# IRSensorModule.net
KiCad netlist of a schematic drawn in EAGLE
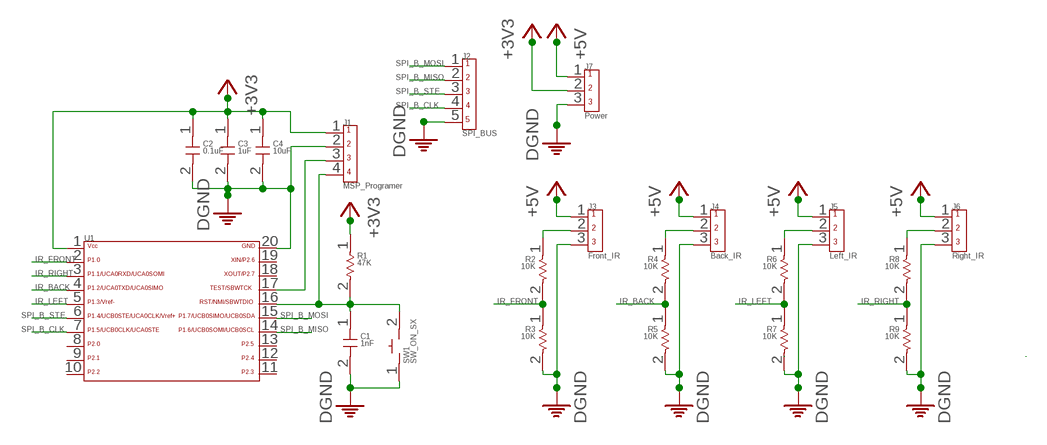
[diagram p0: schematic, sheet 1]

(export (version "E")
  (design (tool "Eeschema 10.0.6"))
  (components
    (comp (ref "C1")
      (value "1nF")
      (footprint "eagle-import:0805")
      (libsource (lib "eagle-import") (part "CAPACITOR_FIXED_0805"))
    )
    (comp (ref "C2")
      (value "0.1uF")
      (footprint "eagle-import:0805")
      (libsource (lib "eagle-import") (part "CAPACITOR_FIXED_0805"))
    )
    (comp (ref "C3")
      (value "1uF")
      (footprint "eagle-import:0805")
      (libsource (lib "eagle-import") (part "CAPACITOR_FIXED_0805"))
    )
    (comp (ref "C4")
      (value "10uF")
      (footprint "eagle-import:0805")
      (libsource (lib "eagle-import") (part "CAPACITOR_FIXED_0805"))
    )
    (comp (ref "J1")
      (value "MSP_Programer")
      (footprint "eagle-import:CON_HEADER_4_100")
      (libsource (lib "eagle-import") (part "CON_HEADER_4PIN_100"))
    )
    (comp (ref "J2")
      (value "SPI_BUS")
      (footprint "eagle-import:CON_HEADER_5_100")
      (libsource (lib "eagle-import") (part "CON_HEADER_5PIN_100"))
    )
    (comp (ref "J3")
      (value "Front_IR")
      (footprint "eagle-import:CON_HEADER_3_100")
      (libsource (lib "eagle-import") (part "CON_HEADER_3PIN_100"))
    )
    (comp (ref "J4")
      (value "Back_IR")
      (footprint "eagle-import:CON_HEADER_3_100")
      (libsource (lib "eagle-import") (part "CON_HEADER_3PIN_100"))
    )
    (comp (ref "J5")
      (value "Left_IR")
      (footprint "eagle-import:CON_HEADER_3_100")
      (libsource (lib "eagle-import") (part "CON_HEADER_3PIN_100"))
    )
    (comp (ref "J6")
      (value "Right_IR")
      (footprint "eagle-import:CON_HEADER_3_100")
      (libsource (lib "eagle-import") (part "CON_HEADER_3PIN_100"))
    )
    (comp (ref "J7")
      (value "Power")
      (footprint "eagle-import:CON_HEADER_3_100")
      (libsource (lib "eagle-import") (part "CON_HEADER_3PIN_100"))
    )
    (comp (ref "R1")
      (value "47K")
      (footprint "eagle-import:0805")
      (libsource (lib "eagle-import") (part "RESISTOR_0805"))
    )
    (comp (ref "R2")
      (value "10K")
      (footprint "eagle-import:0805")
      (libsource (lib "eagle-import") (part "RESISTOR_0805"))
    )
    (comp (ref "R3")
      (value "10K")
      (footprint "eagle-import:0805")
      (libsource (lib "eagle-import") (part "RESISTOR_0805"))
    )
    (comp (ref "R4")
      (value "10K")
      (footprint "eagle-import:0805")
      (libsource (lib "eagle-import") (part "RESISTOR_0805"))
    )
    (comp (ref "R5")
      (value "10K")
      (footprint "eagle-import:0805")
      (libsource (lib "eagle-import") (part "RESISTOR_0805"))
    )
    (comp (ref "R6")
      (value "10K")
      (footprint "eagle-import:0805")
      (libsource (lib "eagle-import") (part "RESISTOR_0805"))
    )
    (comp (ref "R7")
      (value "10K")
      (footprint "eagle-import:0805")
      (libsource (lib "eagle-import") (part "RESISTOR_0805"))
    )
    (comp (ref "R8")
      (value "10K")
      (footprint "eagle-import:0805")
      (libsource (lib "eagle-import") (part "RESISTOR_0805"))
    )
    (comp (ref "R9")
      (value "10K")
      (footprint "eagle-import:0805")
      (libsource (lib "eagle-import") (part "RESISTOR_0805"))
    )
    (comp (ref "SW1")
      (value "SW_ON_SX")
      (footprint "eagle-import:SW_S")
      (libsource (lib "eagle-import") (part "SW_ON_SX"))
    )
    (comp (ref "U1")
      (value "MSP430G2X53/G2X13_20PIN")
      (footprint "eagle-import:SSOP-20")
      (libsource (lib "eagle-import") (part "MSP430G2X53/G2X13_20PIN"))
    )
  )
  (nets
    (net (code "1") (name "+3V3") (class "Default")
      (node (ref "C2") (pin "1") (pinfunction "1_1") (pintype "passive"))
      (node (ref "C3") (pin "1") (pinfunction "1_1") (pintype "passive"))
      (node (ref "C4") (pin "1") (pinfunction "1_1") (pintype "passive"))
      (node (ref "J1") (pin "1") (pinfunction "1_1") (pintype "passive"))
      (node (ref "J7") (pin "2") (pinfunction "2_2") (pintype "passive"))
      (node (ref "R1") (pin "1") (pinfunction "1_1") (pintype "passive"))
      (node (ref "U1") (pin "1") (pinfunction "1_1") (pintype "passive"))
    )
    (net (code "2") (name "+5V") (class "Default")
      (node (ref "J3") (pin "1") (pinfunction "1_1") (pintype "passive"))
      (node (ref "J4") (pin "1") (pinfunction "1_1") (pintype "passive"))
      (node (ref "J5") (pin "1") (pinfunction "1_1") (pintype "passive"))
      (node (ref "J6") (pin "1") (pinfunction "1_1") (pintype "passive"))
      (node (ref "J7") (pin "1") (pinfunction "1_1") (pintype "passive"))
    )
    (net (code "3") (name "/IR_BACK") (class "Default")
      (node (ref "R4") (pin "2") (pinfunction "2_2") (pintype "passive"))
      (node (ref "R5") (pin "1") (pinfunction "1_1") (pintype "passive"))
      (node (ref "U1") (pin "4") (pinfunction "4_4") (pintype "passive"))
    )
    (net (code "4") (name "/IR_FRONT") (class "Default")
      (node (ref "R2") (pin "2") (pinfunction "2_2") (pintype "passive"))
      (node (ref "R3") (pin "1") (pinfunction "1_1") (pintype "passive"))
      (node (ref "U1") (pin "2") (pinfunction "2_2") (pintype "passive"))
    )
    (net (code "5") (name "/IR_LEFT") (class "Default")
      (node (ref "R6") (pin "2") (pinfunction "2_2") (pintype "passive"))
      (node (ref "R7") (pin "1") (pinfunction "1_1") (pintype "passive"))
      (node (ref "U1") (pin "5") (pinfunction "5_5") (pintype "passive"))
    )
    (net (code "6") (name "/IR_RIGHT") (class "Default")
      (node (ref "R8") (pin "2") (pinfunction "2_2") (pintype "passive"))
      (node (ref "R9") (pin "1") (pinfunction "1_1") (pintype "passive"))
      (node (ref "U1") (pin "3") (pinfunction "3_3") (pintype "passive"))
    )
    (net (code "7") (name "/SPI_B_CLK") (class "Default")
      (node (ref "J2") (pin "4") (pinfunction "4_4") (pintype "passive"))
      (node (ref "U1") (pin "7") (pinfunction "7_7") (pintype "passive"))
    )
    (net (code "8") (name "/SPI_B_MISO") (class "Default")
      (node (ref "J2") (pin "2") (pinfunction "2_2") (pintype "passive"))
      (node (ref "U1") (pin "14") (pinfunction "14_14") (pintype "passive"))
    )
    (net (code "9") (name "/SPI_B_MOSI") (class "Default")
      (node (ref "J2") (pin "1") (pinfunction "1_1") (pintype "passive"))
      (node (ref "U1") (pin "15") (pinfunction "15_15") (pintype "passive"))
    )
    (net (code "10") (name "/SPI_B_STE") (class "Default")
      (node (ref "J2") (pin "3") (pinfunction "3_3") (pintype "passive"))
      (node (ref "U1") (pin "6") (pinfunction "6_6") (pintype "passive"))
    )
    (net (code "11") (name "DGND") (class "Default")
      (node (ref "C1") (pin "2") (pinfunction "2_2") (pintype "passive"))
      (node (ref "C2") (pin "2") (pinfunction "2_2") (pintype "passive"))
      (node (ref "C3") (pin "2") (pinfunction "2_2") (pintype "passive"))
      (node (ref "C4") (pin "2") (pinfunction "2_2") (pintype "passive"))
      (node (ref "J1") (pin "2") (pinfunction "2_2") (pintype "passive"))
      (node (ref "J2") (pin "5") (pinfunction "5_5") (pintype "passive"))
      (node (ref "J3") (pin "3") (pinfunction "3_3") (pintype "passive"))
      (node (ref "J4") (pin "3") (pinfunction "3_3") (pintype "passive"))
      (node (ref "J5") (pin "3") (pinfunction "3_3") (pintype "passive"))
      (node (ref "J6") (pin "3") (pinfunction "3_3") (pintype "passive"))
      (node (ref "J7") (pin "3") (pinfunction "3_3") (pintype "passive"))
      (node (ref "R3") (pin "2") (pinfunction "2_2") (pintype "passive"))
      (node (ref "R5") (pin "2") (pinfunction "2_2") (pintype "passive"))
      (node (ref "R7") (pin "2") (pinfunction "2_2") (pintype "passive"))
      (node (ref "R9") (pin "2") (pinfunction "2_2") (pintype "passive"))
      (node (ref "SW1") (pin "1") (pinfunction "1_1") (pintype "passive"))
      (node (ref "U1") (pin "20") (pinfunction "20_20") (pintype "passive"))
    )
    (net (code "12") (name "Net-(C1-Pad1)") (class "Default")
      (node (ref "C1") (pin "1") (pinfunction "1_1") (pintype "passive"))
      (node (ref "J1") (pin "4") (pinfunction "4_4") (pintype "passive"))
      (node (ref "R1") (pin "2") (pinfunction "2_2") (pintype "passive"))
      (node (ref "SW1") (pin "2") (pinfunction "2_2") (pintype "passive"))
      (node (ref "U1") (pin "16") (pinfunction "16_16") (pintype "passive"))
    )
    (net (code "13") (name "Net-(J1-Pad3)") (class "Default")
      (node (ref "J1") (pin "3") (pinfunction "3_3") (pintype "passive"))
      (node (ref "U1") (pin "17") (pinfunction "17_17") (pintype "passive"))
    )
    (net (code "14") (name "Net-(J3-Pad2)") (class "Default")
      (node (ref "J3") (pin "2") (pinfunction "2_2") (pintype "passive"))
      (node (ref "R2") (pin "1") (pinfunction "1_1") (pintype "passive"))
    )
    (net (code "15") (name "Net-(J4-Pad2)") (class "Default")
      (node (ref "J4") (pin "2") (pinfunction "2_2") (pintype "passive"))
      (node (ref "R4") (pin "1") (pinfunction "1_1") (pintype "passive"))
    )
    (net (code "16") (name "Net-(J5-Pad2)") (class "Default")
      (node (ref "J5") (pin "2") (pinfunction "2_2") (pintype "passive"))
      (node (ref "R6") (pin "1") (pinfunction "1_1") (pintype "passive"))
    )
    (net (code "17") (name "Net-(J6-Pad2)") (class "Default")
      (node (ref "J6") (pin "2") (pinfunction "2_2") (pintype "passive"))
      (node (ref "R8") (pin "1") (pinfunction "1_1") (pintype "passive"))
    )
    (net (code "18") (name "unconnected-(U1-Pad8)") (class "Default")
      (node (ref "U1") (pin "8") (pinfunction "8_8") (pintype "passive"))
    )
    (net (code "19") (name "unconnected-(U1-Pad9)") (class "Default")
      (node (ref "U1") (pin "9") (pinfunction "9_9") (pintype "passive"))
    )
    (net (code "20") (name "unconnected-(U1-Pad10)") (class "Default")
      (node (ref "U1") (pin "10") (pinfunction "10_10") (pintype "passive"))
    )
    (net (code "21") (name "unconnected-(U1-Pad11)") (class "Default")
      (node (ref "U1") (pin "11") (pinfunction "11_11") (pintype "passive"))
    )
    (net (code "22") (name "unconnected-(U1-Pad12)") (class "Default")
      (node (ref "U1") (pin "12") (pinfunction "12_12") (pintype "passive"))
    )
    (net (code "23") (name "unconnected-(U1-Pad13)") (class "Default")
      (node (ref "U1") (pin "13") (pinfunction "13_13") (pintype "passive"))
    )
    (net (code "24") (name "unconnected-(U1-Pad18)") (class "Default")
      (node (ref "U1") (pin "18") (pinfunction "18_18") (pintype "passive"))
    )
    (net (code "25") (name "unconnected-(U1-Pad19)") (class "Default")
      (node (ref "U1") (pin "19") (pinfunction "19_19") (pintype "passive"))
    )
  )
)
